# Sheet2-sensor.net
KiCad netlist of a schematic drawn in Altium Designer
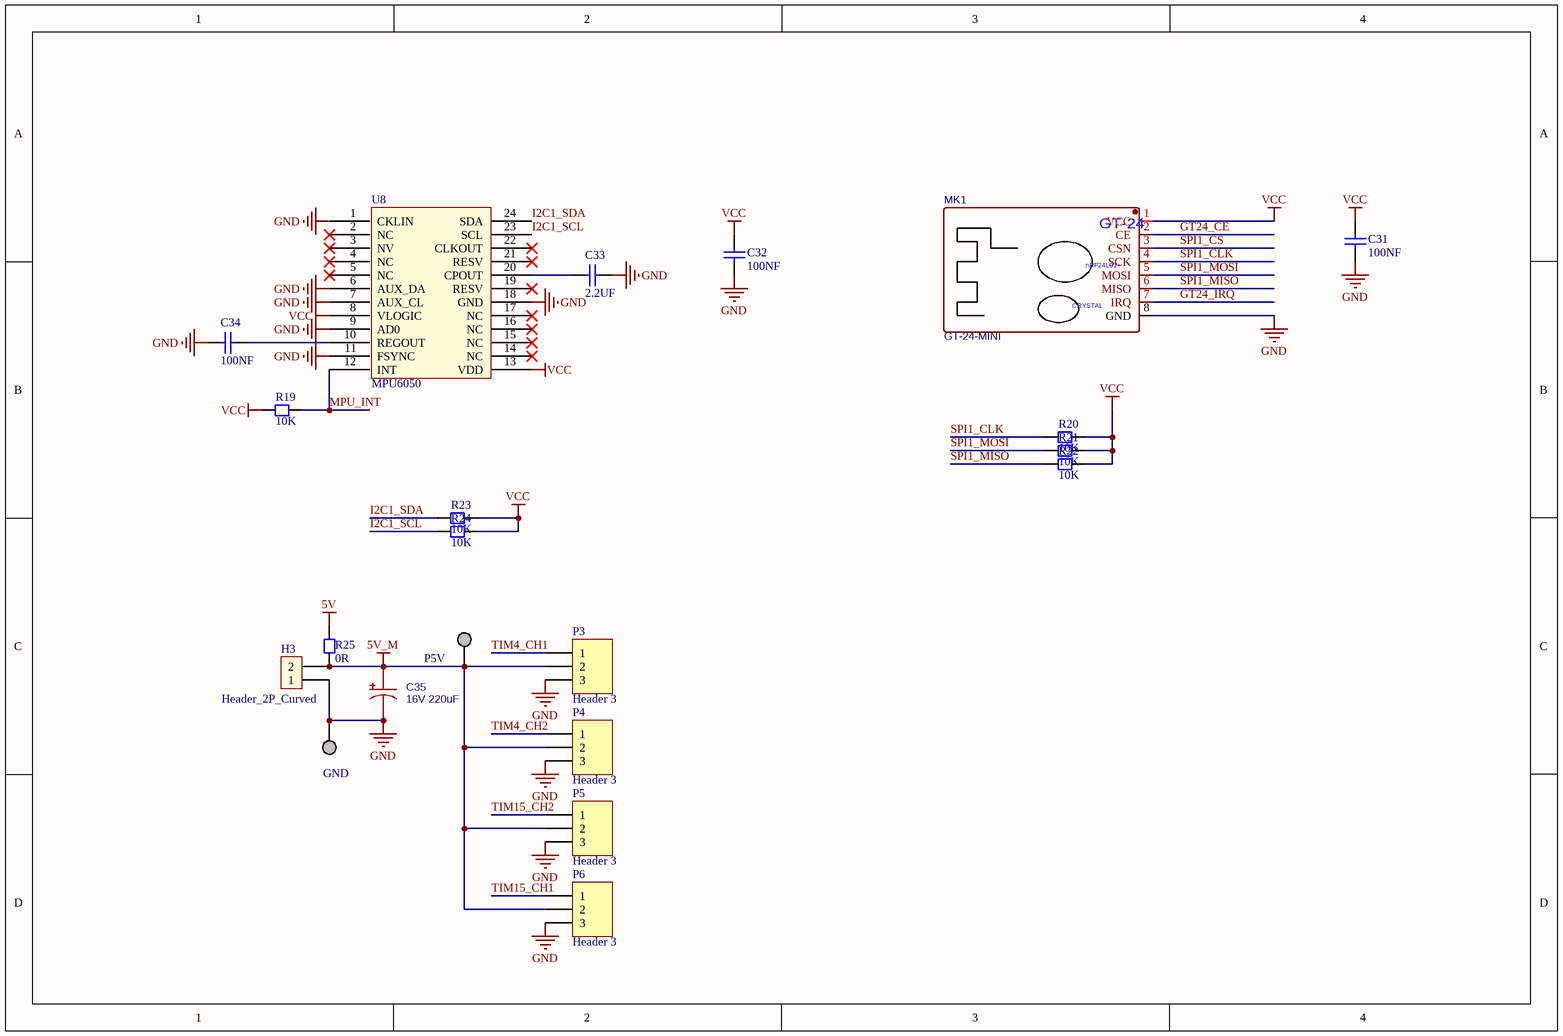
[diagram p0: Sheet2-sensor.SchDoc]

(export (version "E")
  (design (tool "Eeschema 10.0.6"))
  (components
    (comp (ref "C31")
      (value "100NF")
      (footprint "CC1608-0603")
      (description "贴片电容")
      (libsource (lib "tianxiaohua_Schlib") (part "Chip capacitor"))
    )
    (comp (ref "C32")
      (value "100NF")
      (footprint "CC1608-0603")
      (description "贴片电容")
      (libsource (lib "tianxiaohua_Schlib") (part "Chip capacitor"))
    )
    (comp (ref "C33")
      (value "2.2UF")
      (footprint "CC1608-0603")
      (description "贴片电容")
      (libsource (lib "tianxiaohua_Schlib") (part "Chip capacitor"))
    )
    (comp (ref "C34")
      (value "100NF")
      (footprint "CC1608-0603")
      (description "贴片电容")
      (libsource (lib "tianxiaohua_Schlib") (part "Chip capacitor"))
    )
    (comp (ref "C35")
      (value "16V 220uF")
      (footprint "CAP-SMD_D6.3")
      (description "铝点解电容")
      (fields
        (field (name "BOM_SUPPLIER PART") "C413527")
        (field (name "BOM_MANUFACTURER PART") "EEEFP1C681AP")
        (field (name "CONTRIBUTOR") "LCSC")
      )
      (libsource (lib "base") (part "Cap ECAP SMD"))
    )
    (comp (ref "GND")
      (value "test")
      (footprint "test")
      (description "测试点")
      (libsource (lib "base") (part "test"))
    )
    (comp (ref "H3")
      (value "Header_2P_Curved")
      (footprint "Header_2_54_2PW")
      (description "弯的2P排针")
      (libsource (lib "base") (part "Header_2P_Curved"))
    )
    (comp (ref "MK1")
      (value "GT-24-MINI")
      (footprint "GT24 _MINI")
      (description "工业级GT-24数传无线模块 2.4G NRF24L01&PA+LNA")
      (fields (field (name "MANUFACTURER") "Ashining(泽耀科技)") (field (name "MANUFACTURER PART") "AS01-ML01S"))
      (libsource (lib "sensor") (part "GT-24-MINI"))
    )
    (comp (ref "P3")
      (value "Header 3")
      (footprint "HDR1X3")
      (description "Header, 3-Pin")
      (fields (field (name "PUBLISHER") "Altium Limited"))
      (libsource (lib "Connectors") (part "Header 3"))
    )
    (comp (ref "P4")
      (value "Header 3")
      (footprint "HDR1X3")
      (description "Header, 3-Pin")
      (fields (field (name "PUBLISHER") "Altium Limited"))
      (libsource (lib "Connectors") (part "Header 3"))
    )
    (comp (ref "P5")
      (value "Header 3")
      (footprint "HDR1X3")
      (description "Header, 3-Pin")
      (fields (field (name "PUBLISHER") "Altium Limited"))
      (libsource (lib "Connectors") (part "Header 3"))
    )
    (comp (ref "P5V")
      (value "test")
      (footprint "test")
      (description "测试点")
      (libsource (lib "base") (part "test"))
    )
    (comp (ref "P6")
      (value "Header 3")
      (footprint "HDR1X3")
      (description "Header, 3-Pin")
      (fields (field (name "PUBLISHER") "Altium Limited"))
      (libsource (lib "Connectors") (part "Header 3"))
    )
    (comp (ref "R19")
      (value "10K")
      (footprint "CR1608-0603")
      (description "贴片电阻")
      (libsource (lib "tianxiaohua_Schlib") (part "Chip resistor"))
    )
    (comp (ref "R20")
      (value "10K")
      (footprint "CR1608-0603")
      (description "贴片电阻")
      (libsource (lib "tianxiaohua_Schlib") (part "Chip resistor"))
    )
    (comp (ref "R21")
      (value "10K")
      (footprint "CR1608-0603")
      (description "贴片电阻")
      (libsource (lib "tianxiaohua_Schlib") (part "Chip resistor"))
    )
    (comp (ref "R22")
      (value "10K")
      (footprint "CR1608-0603")
      (description "贴片电阻")
      (libsource (lib "tianxiaohua_Schlib") (part "Chip resistor"))
    )
    (comp (ref "R23")
      (value "10K")
      (footprint "CR1608-0603")
      (description "贴片电阻")
      (libsource (lib "tianxiaohua_Schlib") (part "Chip resistor"))
    )
    (comp (ref "R24")
      (value "10K")
      (footprint "CR1608-0603")
      (description "贴片电阻")
      (libsource (lib "tianxiaohua_Schlib") (part "Chip resistor"))
    )
    (comp (ref "R25")
      (value "0R")
      (footprint "CR1608-0603")
      (description "贴片电阻")
      (libsource (lib "") (part "Chip resistor_1"))
    )
    (comp (ref "U8")
      (value "MPU6050")
      (footprint "QFN24 - duplicate")
      (description "陀螺仪")
      (libsource (lib "tianxiaohua_Schlib") (part "MPU6050"))
    )
  )
  (nets
    (net (code "1") (name "/GT24_CE") (class "Default")
      (node (ref "MK1") (pin "2") (pinfunction "CE_2") (pintype "passive"))
    )
    (net (code "2") (name "/GT24_IRQ") (class "Default")
      (node (ref "MK1") (pin "7") (pinfunction "IRQ_7") (pintype "passive"))
    )
    (net (code "3") (name "/I2C1_SCL") (class "Default")
      (node (ref "R24") (pin "2") (pinfunction "2_2") (pintype "passive"))
      (node (ref "U8") (pin "23") (pinfunction "SCL_23") (pintype "passive"))
    )
    (net (code "4") (name "/I2C1_SDA") (class "Default")
      (node (ref "R23") (pin "2") (pinfunction "2_2") (pintype "passive"))
      (node (ref "U8") (pin "24") (pinfunction "SDA_24") (pintype "passive"))
    )
    (net (code "5") (name "/MPU_INT") (class "Default")
      (node (ref "R19") (pin "1") (pinfunction "1_1") (pintype "passive"))
      (node (ref "U8") (pin "12") (pinfunction "INT_12") (pintype "passive"))
    )
    (net (code "6") (name "/SPI1_CLK") (class "Default")
      (node (ref "MK1") (pin "4") (pinfunction "SCK_4") (pintype "passive"))
      (node (ref "R20") (pin "2") (pinfunction "2_2") (pintype "passive"))
    )
    (net (code "7") (name "/SPI1_CS") (class "Default")
      (node (ref "MK1") (pin "3") (pinfunction "CSN_3") (pintype "passive"))
    )
    (net (code "8") (name "/SPI1_MISO") (class "Default")
      (node (ref "MK1") (pin "6") (pinfunction "MISO_6") (pintype "passive"))
      (node (ref "R22") (pin "2") (pinfunction "2_2") (pintype "passive"))
    )
    (net (code "9") (name "/SPI1_MOSI") (class "Default")
      (node (ref "MK1") (pin "5") (pinfunction "MOSI_5") (pintype "passive"))
      (node (ref "R21") (pin "2") (pinfunction "2_2") (pintype "passive"))
    )
    (net (code "10") (name "/TIM4_CH1") (class "Default")
      (node (ref "P3") (pin "1") (pinfunction "1_1") (pintype "passive"))
    )
    (net (code "11") (name "/TIM4_CH2") (class "Default")
      (node (ref "P4") (pin "1") (pinfunction "1_1") (pintype "passive"))
    )
    (net (code "12") (name "/TIM15_CH1") (class "Default")
      (node (ref "P6") (pin "1") (pinfunction "1_1") (pintype "passive"))
    )
    (net (code "13") (name "/TIM15_CH2") (class "Default")
      (node (ref "P5") (pin "1") (pinfunction "1_1") (pintype "passive"))
    )
    (net (code "14") (name "5V") (class "Default")
      (node (ref "R25") (pin "1") (pinfunction "1_1") (pintype "passive"))
    )
    (net (code "15") (name "5V_M") (class "Default")
      (node (ref "C35") (pin "1") (pinfunction "1_1") (pintype "passive"))
      (node (ref "H3") (pin "2") (pinfunction "2_2") (pintype "passive"))
      (node (ref "P3") (pin "2") (pinfunction "2_2") (pintype "passive"))
      (node (ref "P4") (pin "2") (pinfunction "2_2") (pintype "passive"))
      (node (ref "P5") (pin "2") (pinfunction "2_2") (pintype "passive"))
      (node (ref "P5V") (pin "0") (pinfunction "0_0") (pintype "passive"))
      (node (ref "P6") (pin "2") (pinfunction "2_2") (pintype "passive"))
      (node (ref "R25") (pin "2") (pinfunction "2_2") (pintype "passive"))
    )
    (net (code "16") (name "GND") (class "Default")
      (node (ref "C31") (pin "2") (pinfunction "2_2") (pintype "passive"))
      (node (ref "C32") (pin "2") (pinfunction "2_2") (pintype "passive"))
      (node (ref "C33") (pin "2") (pinfunction "2_2") (pintype "passive"))
      (node (ref "C34") (pin "1") (pinfunction "1_1") (pintype "passive"))
      (node (ref "C35") (pin "2") (pinfunction "2_2") (pintype "passive"))
      (node (ref "GND") (pin "0") (pinfunction "0_0") (pintype "passive"))
      (node (ref "H3") (pin "1") (pinfunction "1_1") (pintype "passive"))
      (node (ref "MK1") (pin "8") (pinfunction "GND_8") (pintype "passive"))
      (node (ref "P3") (pin "3") (pinfunction "3_3") (pintype "passive"))
      (node (ref "P4") (pin "3") (pinfunction "3_3") (pintype "passive"))
      (node (ref "P5") (pin "3") (pinfunction "3_3") (pintype "passive"))
      (node (ref "P6") (pin "3") (pinfunction "3_3") (pintype "passive"))
      (node (ref "U8") (pin "1") (pinfunction "CKLIN_1") (pintype "passive"))
      (node (ref "U8") (pin "11") (pinfunction "FSYNC_11") (pintype "passive"))
      (node (ref "U8") (pin "18") (pinfunction "GND_18") (pintype "passive"))
      (node (ref "U8") (pin "6") (pinfunction "AUX_DA_6") (pintype "passive"))
      (node (ref "U8") (pin "7") (pinfunction "AUX_CL_7") (pintype "passive"))
      (node (ref "U8") (pin "9") (pinfunction "AD0_9") (pintype "passive"))
    )
    (net (code "17") (name "Net-(U8-CPOUT)") (class "Default")
      (node (ref "C33") (pin "1") (pinfunction "1_1") (pintype "passive"))
      (node (ref "U8") (pin "20") (pinfunction "CPOUT_20") (pintype "passive"))
    )
    (net (code "18") (name "Net-(U8-REGOUT)") (class "Default")
      (node (ref "C34") (pin "2") (pinfunction "2_2") (pintype "passive"))
      (node (ref "U8") (pin "10") (pinfunction "REGOUT_10") (pintype "passive"))
    )
    (net (code "19") (name "VCC") (class "Default")
      (node (ref "C31") (pin "1") (pinfunction "1_1") (pintype "passive"))
      (node (ref "C32") (pin "1") (pinfunction "1_1") (pintype "passive"))
      (node (ref "MK1") (pin "1") (pinfunction "VCC_1") (pintype "passive"))
      (node (ref "R19") (pin "2") (pinfunction "2_2") (pintype "passive"))
      (node (ref "R20") (pin "1") (pinfunction "1_1") (pintype "passive"))
      (node (ref "R21") (pin "1") (pinfunction "1_1") (pintype "passive"))
      (node (ref "R22") (pin "1") (pinfunction "1_1") (pintype "passive"))
      (node (ref "R23") (pin "1") (pinfunction "1_1") (pintype "passive"))
      (node (ref "R24") (pin "1") (pinfunction "1_1") (pintype "passive"))
      (node (ref "U8") (pin "13") (pinfunction "VDD_13") (pintype "passive"))
      (node (ref "U8") (pin "8") (pinfunction "VLOGIC_8") (pintype "passive"))
    )
    (net (code "20") (name "unconnected-(U8-CLKOUT-Pad22)") (class "Default")
      (node (ref "U8") (pin "22") (pinfunction "CLKOUT_22") (pintype "passive+no_connect"))
    )
    (net (code "21") (name "unconnected-(U8-NC-Pad2)") (class "Default")
      (node (ref "U8") (pin "2") (pinfunction "NC_2") (pintype "passive+no_connect"))
    )
    (net (code "22") (name "unconnected-(U8-NC-Pad4)") (class "Default")
      (node (ref "U8") (pin "4") (pinfunction "NC_4") (pintype "passive+no_connect"))
    )
    (net (code "23") (name "unconnected-(U8-NC-Pad5)") (class "Default")
      (node (ref "U8") (pin "5") (pinfunction "NC_5") (pintype "passive+no_connect"))
    )
    (net (code "24") (name "unconnected-(U8-NC-Pad14)") (class "Default")
      (node (ref "U8") (pin "14") (pinfunction "NC_14") (pintype "passive+no_connect"))
    )
    (net (code "25") (name "unconnected-(U8-NC-Pad15)") (class "Default")
      (node (ref "U8") (pin "15") (pinfunction "NC_15") (pintype "passive+no_connect"))
    )
    (net (code "26") (name "unconnected-(U8-NC-Pad16)") (class "Default")
      (node (ref "U8") (pin "16") (pinfunction "NC_16") (pintype "passive+no_connect"))
    )
    (net (code "27") (name "unconnected-(U8-NC-Pad17)") (class "Default")
      (node (ref "U8") (pin "17") (pinfunction "NC_17") (pintype "passive+no_connect"))
    )
    (net (code "28") (name "unconnected-(U8-NV-Pad3)") (class "Default")
      (node (ref "U8") (pin "3") (pinfunction "NV_3") (pintype "passive+no_connect"))
    )
    (net (code "29") (name "unconnected-(U8-RESV-Pad19)") (class "Default")
      (node (ref "U8") (pin "19") (pinfunction "RESV_19") (pintype "passive+no_connect"))
    )
    (net (code "30") (name "unconnected-(U8-RESV-Pad21)") (class "Default")
      (node (ref "U8") (pin "21") (pinfunction "RESV_21") (pintype "passive+no_connect"))
    )
  )
)
